# UsbEuroPowerAdapter.net
KiCad netlist of a schematic drawn in EAGLE
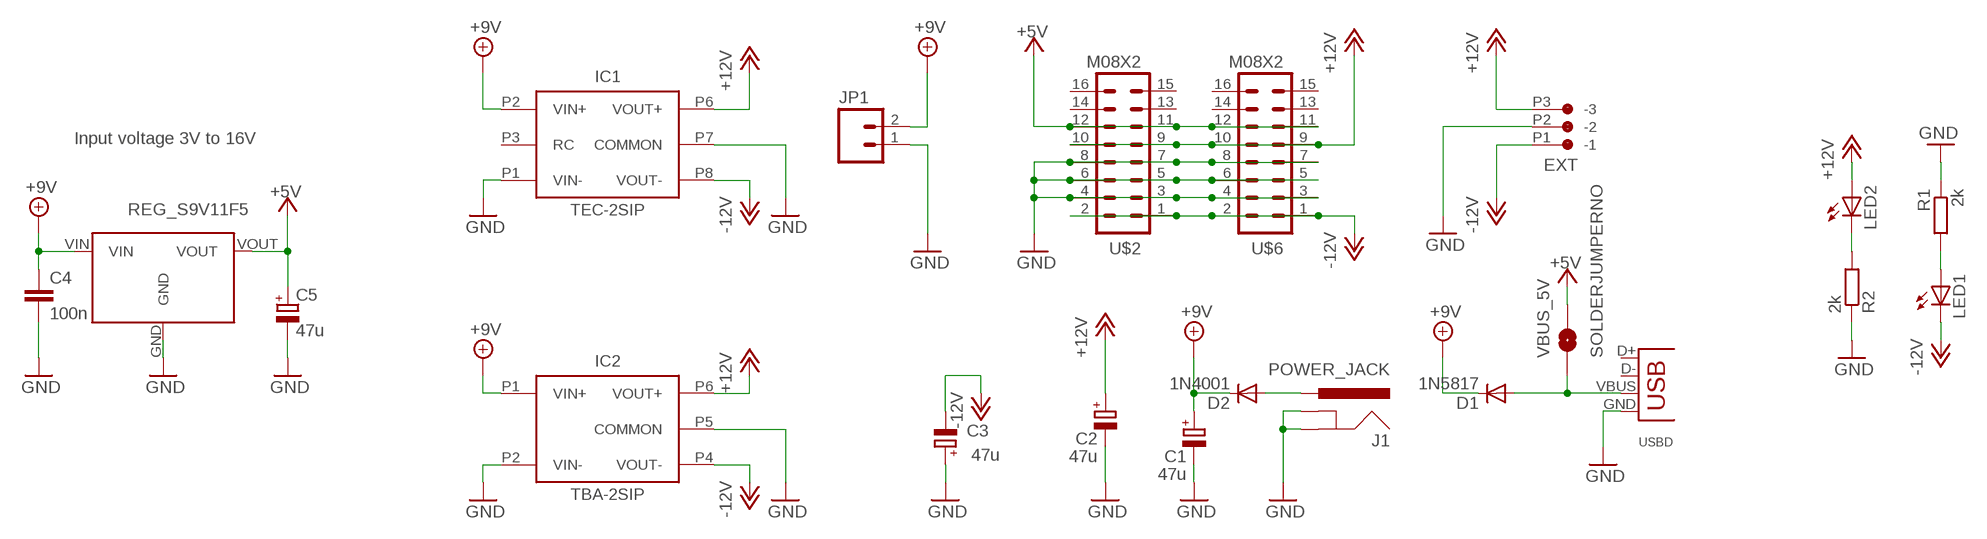
[diagram p0: schematic, sheet 1]

(export (version "E")
  (design (tool "Eeschema 10.0.6"))
  (components
    (comp (ref "C1")
      (value "47u")
      (footprint "eagle-import:E5-6")
      (libsource (lib "eagle-import") (part "CPOL-EUE5-6"))
    )
    (comp (ref "C2")
      (value "47u")
      (footprint "eagle-import:E5-6")
      (libsource (lib "eagle-import") (part "CPOL-EUE5-6"))
    )
    (comp (ref "C3")
      (value "47u")
      (footprint "eagle-import:E5-6")
      (libsource (lib "eagle-import") (part "CPOL-EUE5-6"))
    )
    (comp (ref "C4")
      (value "100n")
      (footprint "eagle-import:C050-024X044")
      (libsource (lib "eagle-import") (part "C-EU050-024X044"))
    )
    (comp (ref "C5")
      (value "47u")
      (footprint "eagle-import:E5-6")
      (libsource (lib "eagle-import") (part "CPOL-EUE5-6"))
    )
    (comp (ref "D1")
      (value "1N5817")
      (footprint "eagle-import:DIODE-1N4001")
      (libsource (lib "eagle-import") (part "DIODEPTH"))
    )
    (comp (ref "D2")
      (value "1N4001")
      (footprint "eagle-import:DIODE-1N4001")
      (libsource (lib "eagle-import") (part "DIODEPTH"))
    )
    (comp (ref "EXT")
      (value "CON-JST_PH_3W")
      (footprint "eagle-import:CON-JST_PH_3W")
      (libsource (lib "eagle-import") (part "CON-JST_PH_3W"))
    )
    (comp (ref "IC1")
      (value "TEC-2SIP")
      (footprint "eagle-import:TEC-2")
      (libsource (lib "eagle-import") (part "TEC-2SIP"))
    )
    (comp (ref "IC2")
      (value "TBA-2SIP")
      (footprint "eagle-import:TBA-2")
      (libsource (lib "eagle-import") (part "TBA-2SIP"))
    )
    (comp (ref "IC3")
      (value "REG_S9V11F5")
      (footprint "eagle-import:REG_S9V11F5")
      (libsource (lib "eagle-import") (part "REG_S9V11F5"))
    )
    (comp (ref "J1")
      (value "POWER_JACK")
      (footprint "eagle-import:DC_JACK_SLOT")
      (libsource (lib "eagle-import") (part "POWER_JACK"))
    )
    (comp (ref "JP1")
      (value "M02PTH")
      (footprint "eagle-import:1X02")
      (libsource (lib "eagle-import") (part "M02PTH"))
    )
    (comp (ref "LED1")
      (value "LED3MM")
      (footprint "eagle-import:LED3MM")
      (libsource (lib "eagle-import") (part "LED3MM"))
    )
    (comp (ref "LED2")
      (value "LED3MM")
      (footprint "eagle-import:LED3MM")
      (libsource (lib "eagle-import") (part "LED3MM"))
    )
    (comp (ref "R1")
      (value "2k")
      (footprint "eagle-import:0204_7")
      (libsource (lib "eagle-import") (part "R-EU_0204/7"))
    )
    (comp (ref "R2")
      (value "2k")
      (footprint "eagle-import:0204_7")
      (libsource (lib "eagle-import") (part "R-EU_0204/7"))
    )
    (comp (ref "U$2")
      (value "M08X2")
      (footprint "eagle-import:2X8")
      (libsource (lib "eagle-import") (part "M08X2"))
    )
    (comp (ref "U$6")
      (value "M08X2")
      (footprint "eagle-import:2X8")
      (libsource (lib "eagle-import") (part "M08X2"))
    )
    (comp (ref "USBD")
      (value "USB-B-H")
      (footprint "eagle-import:USB-B-H")
      (libsource (lib "eagle-import") (part "USB-B-H"))
    )
    (comp (ref "VBUS_5V")
      (value "SOLDERJUMPERNO")
      (footprint "eagle-import:SJ_2S-NO")
      (libsource (lib "eagle-import") (part "SOLDERJUMPERNO"))
    )
  )
  (nets
    (net (code "1") (name "+5V") (class "Default")
      (node (ref "C5") (pin "+") (pinfunction "+_+") (pintype "passive"))
      (node (ref "IC3") (pin "VOUT") (pinfunction "VOUT_VOUT") (pintype "output"))
      (node (ref "U$2") (pin "11") (pinfunction "11_11") (pintype "passive"))
      (node (ref "U$2") (pin "12") (pinfunction "12_12") (pintype "passive"))
      (node (ref "U$6") (pin "11") (pinfunction "11_11") (pintype "passive"))
      (node (ref "U$6") (pin "12") (pinfunction "12_12") (pintype "passive"))
      (node (ref "VBUS_5V") (pin "2") (pinfunction "2_2") (pintype "passive"))
    )
    (net (code "2") (name "+9V") (class "Default")
      (node (ref "C1") (pin "+") (pinfunction "+_+") (pintype "passive"))
      (node (ref "C4") (pin "1") (pinfunction "1_1") (pintype "passive"))
      (node (ref "D1") (pin "C") (pinfunction "C_C") (pintype "passive"))
      (node (ref "D2") (pin "C") (pinfunction "C_C") (pintype "passive"))
      (node (ref "IC1") (pin "P2") (pinfunction "VIN+_P2") (pintype "bidirectional"))
      (node (ref "IC2") (pin "P1") (pinfunction "VIN+_P1") (pintype "bidirectional"))
      (node (ref "IC3") (pin "VIN") (pinfunction "VIN_VIN") (pintype "input"))
      (node (ref "JP1") (pin "2") (pinfunction "2_2") (pintype "passive"))
    )
    (net (code "3") (name "+12V") (class "Default")
      (node (ref "C2") (pin "+") (pinfunction "+_+") (pintype "passive"))
      (node (ref "EXT") (pin "P3") (pinfunction "-3_P3") (pintype "bidirectional"))
      (node (ref "IC1") (pin "P6") (pinfunction "VOUT+_P6") (pintype "bidirectional"))
      (node (ref "IC2") (pin "P6") (pinfunction "VOUT+_P6") (pintype "bidirectional"))
      (node (ref "LED2") (pin "A") (pinfunction "A_A") (pintype "passive"))
      (node (ref "U$2") (pin "10") (pinfunction "10_10") (pintype "passive"))
      (node (ref "U$2") (pin "9") (pinfunction "9_9") (pintype "passive"))
      (node (ref "U$6") (pin "10") (pinfunction "10_10") (pintype "passive"))
      (node (ref "U$6") (pin "9") (pinfunction "9_9") (pintype "passive"))
    )
    (net (code "4") (name "-12V") (class "Default")
      (node (ref "C3") (pin "-") (pinfunction "-_-") (pintype "passive"))
      (node (ref "EXT") (pin "P1") (pinfunction "-1_P1") (pintype "bidirectional"))
      (node (ref "IC1") (pin "P8") (pinfunction "VOUT-_P8") (pintype "bidirectional"))
      (node (ref "IC2") (pin "P4") (pinfunction "VOUT-_P4") (pintype "bidirectional"))
      (node (ref "LED1") (pin "K") (pinfunction "C_K") (pintype "passive"))
      (node (ref "U$2") (pin "1") (pinfunction "1_1") (pintype "passive"))
      (node (ref "U$2") (pin "2") (pinfunction "2_2") (pintype "passive"))
      (node (ref "U$6") (pin "1") (pinfunction "1_1") (pintype "passive"))
      (node (ref "U$6") (pin "2") (pinfunction "2_2") (pintype "passive"))
    )
    (net (code "5") (name "GND") (class "Default")
      (node (ref "C1") (pin "-") (pinfunction "-_-") (pintype "passive"))
      (node (ref "C2") (pin "-") (pinfunction "-_-") (pintype "passive"))
      (node (ref "C3") (pin "+") (pinfunction "+_+") (pintype "passive"))
      (node (ref "C4") (pin "2") (pinfunction "2_2") (pintype "passive"))
      (node (ref "C5") (pin "-") (pinfunction "-_-") (pintype "passive"))
      (node (ref "EXT") (pin "P2") (pinfunction "-2_P2") (pintype "bidirectional"))
      (node (ref "IC1") (pin "P1") (pinfunction "VIN-_P1") (pintype "bidirectional"))
      (node (ref "IC1") (pin "P7") (pinfunction "COMMON_P7") (pintype "bidirectional"))
      (node (ref "IC2") (pin "P2") (pinfunction "VIN-_P2") (pintype "bidirectional"))
      (node (ref "IC2") (pin "P5") (pinfunction "COMMON_P5") (pintype "bidirectional"))
      (node (ref "IC3") (pin "GND") (pinfunction "GND_GND") (pintype "power_in"))
      (node (ref "J1") (pin "GND") (pinfunction "GND_GND") (pintype "bidirectional"))
      (node (ref "J1") (pin "GNDBREAK") (pinfunction "GNDBREAK_GNDBREAK") (pintype "bidirectional"))
      (node (ref "JP1") (pin "1") (pinfunction "1_1") (pintype "passive"))
      (node (ref "R1") (pin "1") (pinfunction "1_1") (pintype "passive"))
      (node (ref "R2") (pin "1") (pinfunction "1_1") (pintype "passive"))
      (node (ref "U$2") (pin "3") (pinfunction "3_3") (pintype "passive"))
      (node (ref "U$2") (pin "4") (pinfunction "4_4") (pintype "passive"))
      (node (ref "U$2") (pin "5") (pinfunction "5_5") (pintype "passive"))
      (node (ref "U$2") (pin "6") (pinfunction "6_6") (pintype "passive"))
      (node (ref "U$2") (pin "7") (pinfunction "7_7") (pintype "passive"))
      (node (ref "U$2") (pin "8") (pinfunction "8_8") (pintype "passive"))
      (node (ref "U$6") (pin "3") (pinfunction "3_3") (pintype "passive"))
      (node (ref "U$6") (pin "4") (pinfunction "4_4") (pintype "passive"))
      (node (ref "U$6") (pin "5") (pinfunction "5_5") (pintype "passive"))
      (node (ref "U$6") (pin "6") (pinfunction "6_6") (pintype "passive"))
      (node (ref "U$6") (pin "7") (pinfunction "7_7") (pintype "passive"))
      (node (ref "U$6") (pin "8") (pinfunction "8_8") (pintype "passive"))
      (node (ref "USBD") (pin "GND") (pinfunction "GND_GND") (pintype "bidirectional"))
    )
    (net (code "6") (name "Net-(D1-PadA)") (class "Default")
      (node (ref "D1") (pin "A") (pinfunction "A_A") (pintype "passive"))
      (node (ref "USBD") (pin "VBUS") (pinfunction "VBUS_VBUS") (pintype "bidirectional"))
      (node (ref "VBUS_5V") (pin "1") (pinfunction "1_1") (pintype "passive"))
    )
    (net (code "7") (name "Net-(D2-PadA)") (class "Default")
      (node (ref "D2") (pin "A") (pinfunction "A_A") (pintype "passive"))
      (node (ref "J1") (pin "PWR") (pinfunction "PWR_PWR") (pintype "bidirectional"))
    )
    (net (code "8") (name "Net-(LED1-PadA)") (class "Default")
      (node (ref "LED1") (pin "A") (pinfunction "A_A") (pintype "passive"))
      (node (ref "R1") (pin "2") (pinfunction "2_2") (pintype "passive"))
    )
    (net (code "9") (name "Net-(LED2-C)") (class "Default")
      (node (ref "LED2") (pin "K") (pinfunction "C_K") (pintype "passive"))
      (node (ref "R2") (pin "2") (pinfunction "2_2") (pintype "passive"))
    )
    (net (code "10") (name "unconnected-(IC1-RC-PadP3)") (class "Default")
      (node (ref "IC1") (pin "P3") (pinfunction "RC_P3") (pintype "bidirectional"))
    )
    (net (code "11") (name "unconnected-(U$2-Pad13)") (class "Default")
      (node (ref "U$2") (pin "13") (pinfunction "13_13") (pintype "passive"))
    )
    (net (code "12") (name "unconnected-(U$2-Pad14)") (class "Default")
      (node (ref "U$2") (pin "14") (pinfunction "14_14") (pintype "passive"))
    )
    (net (code "13") (name "unconnected-(U$2-Pad15)") (class "Default")
      (node (ref "U$2") (pin "15") (pinfunction "15_15") (pintype "passive"))
    )
    (net (code "14") (name "unconnected-(U$2-Pad16)") (class "Default")
      (node (ref "U$2") (pin "16") (pinfunction "16_16") (pintype "passive"))
    )
    (net (code "15") (name "unconnected-(U$6-Pad13)") (class "Default")
      (node (ref "U$6") (pin "13") (pinfunction "13_13") (pintype "passive"))
    )
    (net (code "16") (name "unconnected-(U$6-Pad14)") (class "Default")
      (node (ref "U$6") (pin "14") (pinfunction "14_14") (pintype "passive"))
    )
    (net (code "17") (name "unconnected-(U$6-Pad15)") (class "Default")
      (node (ref "U$6") (pin "15") (pinfunction "15_15") (pintype "passive"))
    )
    (net (code "18") (name "unconnected-(U$6-Pad16)") (class "Default")
      (node (ref "U$6") (pin "16") (pinfunction "16_16") (pintype "passive"))
    )
    (net (code "19") (name "unconnected-(USBD-PadD+)") (class "Default")
      (node (ref "USBD") (pin "D+") (pinfunction "D+_D+") (pintype "bidirectional"))
    )
    (net (code "20") (name "unconnected-(USBD-PadD-)") (class "Default")
      (node (ref "USBD") (pin "D-") (pinfunction "D-_D-") (pintype "bidirectional"))
    )
  )
)
